# Power.net
KiCad netlist of a schematic drawn in Altium Designer
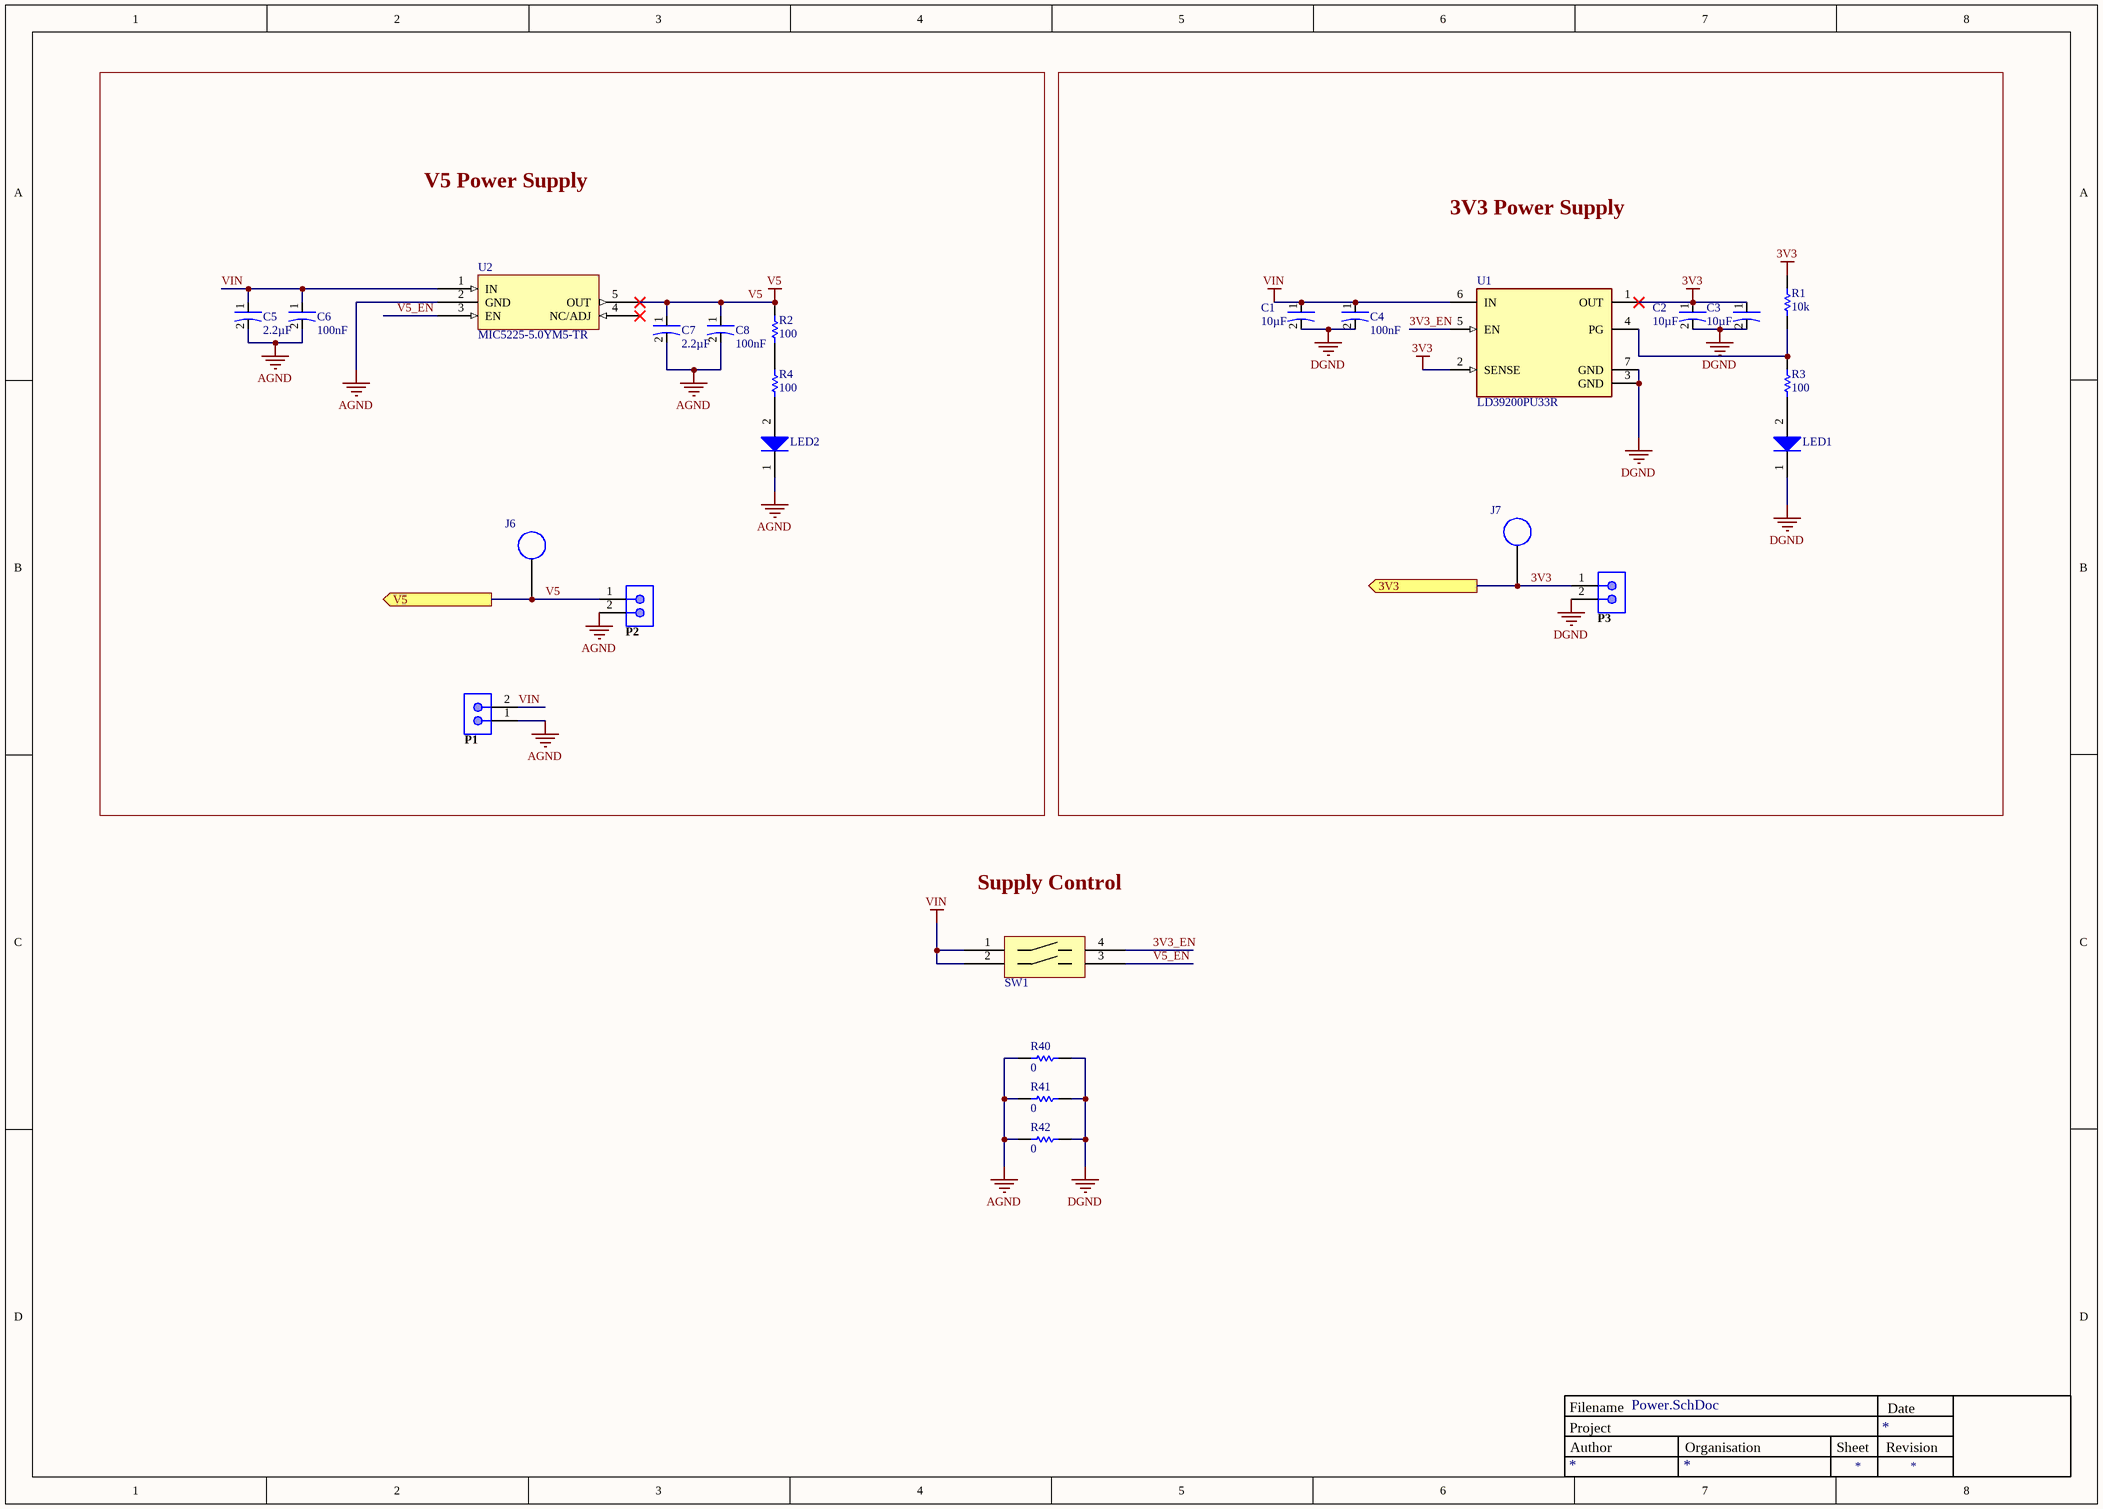
[diagram p0: Power.SchDoc]

(export (version "E")
  (design (tool "Eeschema 10.0.6"))
  (components
    (comp (ref "C1")
      (value "10µF")
      (footprint "0402-M")
      (description "CAP-10uF-CER-0402-6.3V-X5R-20%")
      (fields
        (field (name "MANUFACTURER") "Generic")
        (field (name "Comment") "CAP 10uF CER 0402 6.3V X5R 20%")
      )
      (libsource (lib "") (part "Symbol_1"))
    )
    (comp (ref "C2")
      (value "10µF")
      (footprint "0402-M")
      (description "CAP-10uF-CER-0402-6.3V-X5R-20%")
      (fields
        (field (name "MANUFACTURER") "Generic")
        (field (name "Comment") "CAP 10uF CER 0402 6.3V X5R 20%")
      )
      (libsource (lib "") (part "Symbol_1"))
    )
    (comp (ref "C3")
      (value "10µF")
      (footprint "0402-M")
      (description "CAP-10uF-CER-0402-6.3V-X5R-20%")
      (fields
        (field (name "MANUFACTURER") "Generic")
        (field (name "Comment") "CAP 10uF CER 0402 6.3V X5R 20%")
      )
      (libsource (lib "") (part "Symbol_1"))
    )
    (comp (ref "C4")
      (value "100nF")
      (footprint "0402-M")
      (description "CAP-0.1uF-CER-0402-16V-X5R-10%")
      (fields
        (field (name "MANUFACTURER") "Generic")
        (field (name "Comment") "CAP 0.1uF CER 0402 16V X5R 10%")
      )
      (libsource (lib "") (part "Symbol_1"))
    )
    (comp (ref "C5")
      (value "2.2µF")
      (footprint "0402-M")
      (description "CAP-2.2uF-CER-0402-25V-X5R-10%")
      (fields
        (field (name "MANUFACTURER") "Generic")
        (field (name "Comment") "CAP 2.2uF CER 0402 25V X5R 10%")
      )
      (libsource (lib "") (part "Symbol_1"))
    )
    (comp (ref "C6")
      (value "100nF")
      (footprint "0402-M")
      (description "CAP-0.1uF-CER-0402-16V-X5R-10%")
      (fields
        (field (name "MANUFACTURER") "Generic")
        (field (name "Comment") "CAP 0.1uF CER 0402 16V X5R 10%")
      )
      (libsource (lib "") (part "Symbol_1"))
    )
    (comp (ref "C7")
      (value "2.2µF")
      (footprint "0402-M")
      (description "CAP-2.2uF-CER-0402-25V-X5R-10%")
      (fields
        (field (name "MANUFACTURER") "Generic")
        (field (name "Comment") "CAP 2.2uF CER 0402 25V X5R 10%")
      )
      (libsource (lib "") (part "Symbol_1"))
    )
    (comp (ref "C8")
      (value "100nF")
      (footprint "0402-M")
      (description "CAP-0.1uF-CER-0402-16V-X5R-10%")
      (fields
        (field (name "MANUFACTURER") "Generic")
        (field (name "Comment") "CAP 0.1uF CER 0402 16V X5R 10%")
      )
      (libsource (lib "") (part "Symbol_1"))
    )
    (comp (ref "J6")
      (value "151-203-RC")
      (footprint "151-203-RC-Footprint-1")
      (description "PCB-Probe-Ring")
      (libsource (lib "University of Malta - MEMENTO") (part "PCB Probe Ring"))
    )
    (comp (ref "J7")
      (value "151-203-RC")
      (footprint "151-203-RC-Footprint-1")
      (description "PCB-Probe-Ring")
      (libsource (lib "University of Malta - MEMENTO") (part "PCB Probe Ring"))
    )
    (comp (ref "LED1")
      (value "LED 0603 Green 20mA 1.8V")
      (footprint "0603 Generic")
      (description "LED-0603-Green-20mA-1.8V-STOCK")
      (fields (field (name "MANUFACTURER") "Generic"))
      (libsource (lib "University of Malta - MEMENTO") (part "Symbol"))
    )
    (comp (ref "LED2")
      (value "LED 0603 Green 20mA 1.8V")
      (footprint "0603 Generic")
      (description "LED-0603-Green-20mA-1.8V-STOCK")
      (fields (field (name "MANUFACTURER") "Generic"))
      (libsource (lib "University of Malta - MEMENTO") (part "Symbol"))
    )
    (comp (ref "P1")
      (value "GENERIC 2PIN HEADER MALE")
      (footprint "GENERIC 2PIN HEADER 0")
      (description "CONN MAL TH 2 0Deg HEADER")
      (fields (field (name "MANUFACTURER") "Generic"))
      (libsource (lib "") (part "GENERIC 2PIN HEADER MALE_1"))
    )
    (comp (ref "P2")
      (value "GENERIC 2PIN HEADER MALE")
      (footprint "GENERIC 2PIN HEADER 0")
      (description "CONN MAL TH 2 0Deg HEADER")
      (fields (field (name "MANUFACTURER") "Generic"))
      (libsource (lib "University of Malta - MEMENTO") (part "GENERIC 2PIN HEADER MALE"))
    )
    (comp (ref "P3")
      (value "GENERIC 2PIN HEADER MALE")
      (footprint "GENERIC 2PIN HEADER 0")
      (description "CONN MAL TH 2 0Deg HEADER")
      (fields (field (name "MANUFACTURER") "Generic"))
      (libsource (lib "University of Malta - MEMENTO") (part "GENERIC 2PIN HEADER MALE"))
    )
    (comp (ref "R1")
      (value "10k")
      (footprint "0402-M")
      (description "RES-10k-0402-63mW-5%")
      (fields (field (name "MANUFACTURER") "Generic") (field (name "Comment") "RES 10k 0402 63mW 5%"))
      (libsource (lib "") (part "Symbol_2"))
    )
    (comp (ref "R2")
      (value "100")
      (footprint "0805-L")
      (description "RES-100-0805-125mW-1%")
      (fields (field (name "MANUFACTURER") "Generic") (field (name "Comment") "RES 100 0805 125mW 1%"))
      (libsource (lib "") (part "Symbol_2"))
    )
    (comp (ref "R3")
      (value "100")
      (footprint "0805-L")
      (description "RES-100-0805-125mW-1%")
      (fields (field (name "MANUFACTURER") "Generic") (field (name "Comment") "RES 100 0805 125mW 1%"))
      (libsource (lib "") (part "Symbol_2"))
    )
    (comp (ref "R4")
      (value "100")
      (footprint "0805-L")
      (description "RES-100-0805-125mW-1%")
      (fields (field (name "MANUFACTURER") "Generic") (field (name "Comment") "RES 100 0805 125mW 1%"))
      (libsource (lib "") (part "Symbol_2"))
    )
    (comp (ref "R40")
      (value "0")
      (footprint "0402-M")
      (description "RES-0-0402-63mW-5%")
      (fields (field (name "MANUFACTURER") "Generic") (field (name "Comment") "RES 0 0402 63mW"))
      (libsource (lib "") (part "Symbol_2"))
    )
    (comp (ref "R41")
      (value "0")
      (footprint "0402-M")
      (description "RES-0-0402-63mW-5%")
      (fields (field (name "MANUFACTURER") "Generic") (field (name "Comment") "RES 0 0402 63mW"))
      (libsource (lib "") (part "Symbol_2"))
    )
    (comp (ref "R42")
      (value "0")
      (footprint "0402-M")
      (description "RES-0-0402-63mW-5%")
      (fields (field (name "MANUFACTURER") "Generic") (field (name "Comment") "RES 0 0402 63mW"))
      (libsource (lib "") (part "Symbol_2"))
    )
    (comp (ref "SW1")
      (value "210-2MS")
      (footprint "210-2MS-Footprint-1")
      (description "SWITCH DIP SPST 2 100mA 50V")
      (libsource (lib "University of Malta - MEMENTO") (part "210-2MS"))
    )
    (comp (ref "U1")
      (value "LD39200PU33R")
      (footprint "FP-DFN6-7946637-MFG")
      (description "STMICROELECTRONICS - LD39200PU33R - LDO, FIXED, 3.3V, 2A, -40 TO 125DEG C")
      (fields (field (name "MANUFACTURER") "STMicroelectronics"))
      (libsource (lib "University of Malta - MEMENTO") (part "f0cfe00d12cb984572f50007c934a2d"))
    )
    (comp (ref "U2")
      (value "MIC5225-5.0YM5-TR")
      (footprint "SOT95P280X145-5N")
      (libsource (lib "University of Malta - MEMENTO") (part "MIC5225-5.0YM5-TR"))
    )
  )
  (nets
    (net (code "1") (name "/3V3_EN") (class "Default")
      (node (ref "SW1") (pin "4") (pinfunction "4_4") (pintype "passive"))
      (node (ref "U1") (pin "5") (pinfunction "EN_5") (pintype "input"))
    )
    (net (code "2") (name "/V5_EN") (class "Default")
      (node (ref "SW1") (pin "3") (pinfunction "4_3") (pintype "passive"))
      (node (ref "U2") (pin "3") (pinfunction "EN_3") (pintype "input"))
    )
    (net (code "3") (name "3V3") (class "Default")
      (node (ref "C2") (pin "1") (pinfunction "Anode_1") (pintype "passive"))
      (node (ref "C3") (pin "1") (pinfunction "Anode_1") (pintype "passive"))
      (node (ref "J7") (pin "1") (pinfunction "1_1") (pintype "passive"))
      (node (ref "P3") (pin "1") (pinfunction "1_1") (pintype "passive"))
      (node (ref "R1") (pin "2") (pinfunction "2_2") (pintype "passive"))
      (node (ref "U1") (pin "1") (pinfunction "OUT_1") (pintype "power_in"))
      (node (ref "U1") (pin "2") (pinfunction "SENSE_2") (pintype "input"))
    )
    (net (code "4") (name "AGND") (class "Default")
      (node (ref "C5") (pin "2") (pinfunction "Cathode_2") (pintype "passive"))
      (node (ref "C6") (pin "2") (pinfunction "Cathode_2") (pintype "passive"))
      (node (ref "C7") (pin "2") (pinfunction "Cathode_2") (pintype "passive"))
      (node (ref "C8") (pin "2") (pinfunction "Cathode_2") (pintype "passive"))
      (node (ref "LED2") (pin "1") (pinfunction "1_1") (pintype "passive"))
      (node (ref "P1") (pin "1") (pinfunction "1_1") (pintype "passive"))
      (node (ref "P2") (pin "2") (pinfunction "2_2") (pintype "passive"))
      (node (ref "R40") (pin "1") (pinfunction "1_1") (pintype "passive"))
      (node (ref "R41") (pin "1") (pinfunction "1_1") (pintype "passive"))
      (node (ref "R42") (pin "1") (pinfunction "1_1") (pintype "passive"))
      (node (ref "U2") (pin "2") (pinfunction "GND_2") (pintype "power_in"))
    )
    (net (code "5") (name "DGND") (class "Default")
      (node (ref "C1") (pin "2") (pinfunction "Cathode_2") (pintype "passive"))
      (node (ref "C2") (pin "2") (pinfunction "Cathode_2") (pintype "passive"))
      (node (ref "C3") (pin "2") (pinfunction "Cathode_2") (pintype "passive"))
      (node (ref "C4") (pin "2") (pinfunction "Cathode_2") (pintype "passive"))
      (node (ref "LED1") (pin "1") (pinfunction "1_1") (pintype "passive"))
      (node (ref "P3") (pin "2") (pinfunction "2_2") (pintype "passive"))
      (node (ref "R40") (pin "2") (pinfunction "2_2") (pintype "passive"))
      (node (ref "R41") (pin "2") (pinfunction "2_2") (pintype "passive"))
      (node (ref "R42") (pin "2") (pinfunction "2_2") (pintype "passive"))
      (node (ref "U1") (pin "3") (pinfunction "GND_3") (pintype "power_in"))
      (node (ref "U1") (pin "7") (pinfunction "GND_7") (pintype "power_in"))
    )
    (net (code "6") (name "Net-(LED1-Pad2)") (class "Default")
      (node (ref "LED1") (pin "2") (pinfunction "2_2") (pintype "passive"))
      (node (ref "R3") (pin "1") (pinfunction "1_1") (pintype "passive"))
    )
    (net (code "7") (name "Net-(LED2-Pad2)") (class "Default")
      (node (ref "LED2") (pin "2") (pinfunction "2_2") (pintype "passive"))
      (node (ref "R4") (pin "1") (pinfunction "1_1") (pintype "passive"))
    )
    (net (code "8") (name "Net-(R2-Pad1)") (class "Default")
      (node (ref "R2") (pin "1") (pinfunction "1_1") (pintype "passive"))
      (node (ref "R4") (pin "2") (pinfunction "2_2") (pintype "passive"))
    )
    (net (code "9") (name "Net-(U1-PG)") (class "Default")
      (node (ref "R1") (pin "1") (pinfunction "1_1") (pintype "passive"))
      (node (ref "R3") (pin "2") (pinfunction "2_2") (pintype "passive"))
      (node (ref "U1") (pin "4") (pinfunction "PG_4") (pintype "open_collector"))
    )
    (net (code "10") (name "V5") (class "Default")
      (node (ref "C7") (pin "1") (pinfunction "Anode_1") (pintype "passive"))
      (node (ref "C8") (pin "1") (pinfunction "Anode_1") (pintype "passive"))
      (node (ref "J6") (pin "1") (pinfunction "1_1") (pintype "passive"))
      (node (ref "P2") (pin "1") (pinfunction "1_1") (pintype "passive"))
      (node (ref "R2") (pin "2") (pinfunction "2_2") (pintype "passive"))
      (node (ref "U2") (pin "5") (pinfunction "OUT_5") (pintype "output"))
    )
    (net (code "11") (name "VIN") (class "Default")
      (node (ref "C1") (pin "1") (pinfunction "Anode_1") (pintype "passive"))
      (node (ref "C4") (pin "1") (pinfunction "Anode_1") (pintype "passive"))
      (node (ref "C5") (pin "1") (pinfunction "Anode_1") (pintype "passive"))
      (node (ref "C6") (pin "1") (pinfunction "Anode_1") (pintype "passive"))
      (node (ref "P1") (pin "2") (pinfunction "2_2") (pintype "passive"))
      (node (ref "SW1") (pin "1") (pinfunction "1_1") (pintype "passive"))
      (node (ref "SW1") (pin "2") (pinfunction "2_2") (pintype "passive"))
      (node (ref "U1") (pin "6") (pinfunction "IN_6") (pintype "power_in"))
      (node (ref "U2") (pin "1") (pinfunction "IN_1") (pintype "input"))
    )
    (net (code "12") (name "unconnected-(U2-NC{slash}ADJ-Pad4)") (class "Default")
      (node (ref "U2") (pin "4") (pinfunction "NC/ADJ_4") (pintype "input+no_connect"))
    )
  )
)
